# PennyMan_Ard_R3_Shield_v9_1.net
KiCad netlist of a schematic drawn in EAGLE
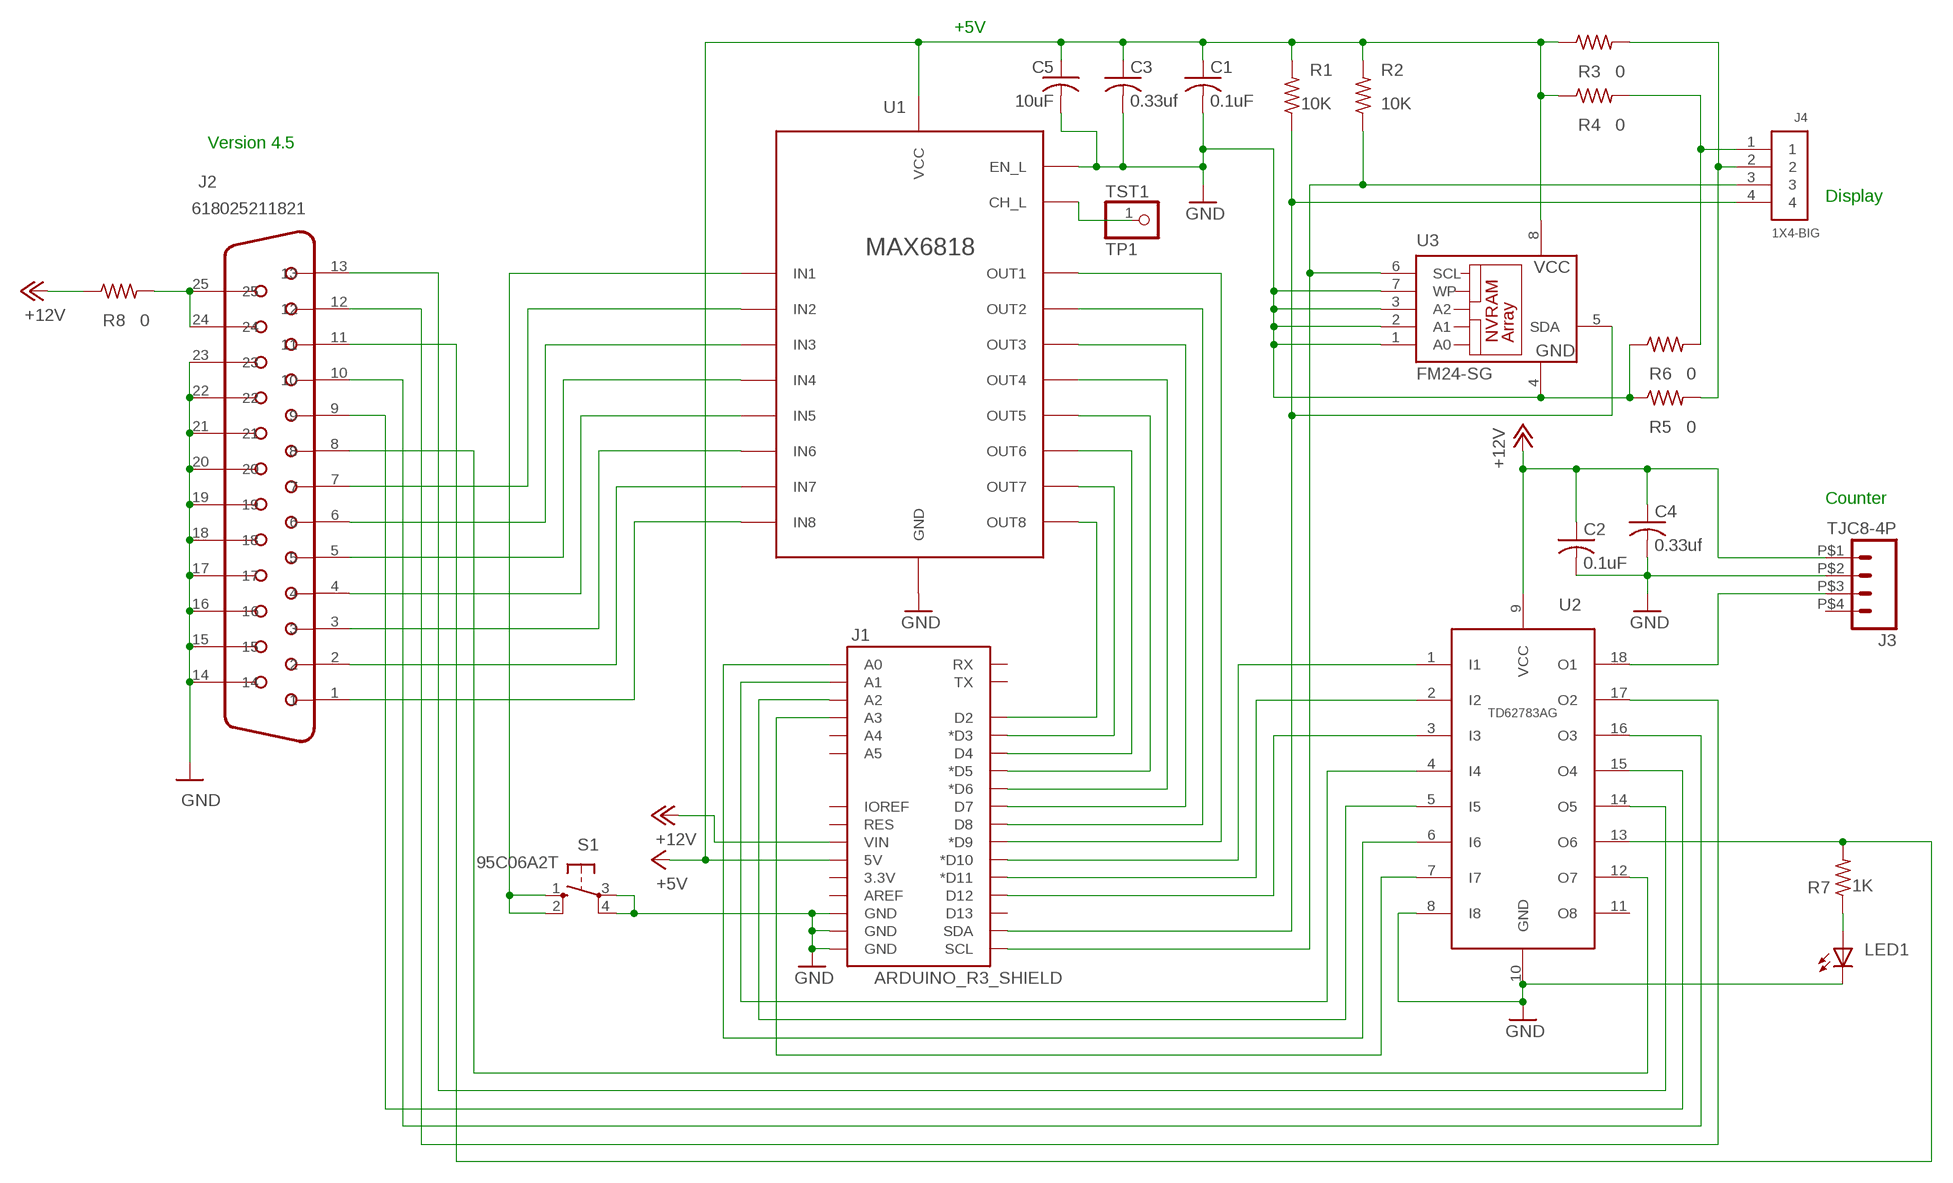
[diagram p0: schematic, sheet 1]

(export (version "E")
  (design (tool "Eeschema 10.0.6"))
  (components
    (comp (ref "C1")
      (value "0.1uF")
      (footprint "eagle-import:C0805")
      (libsource (lib "eagle-import") (part "C-USC0805"))
    )
    (comp (ref "C2")
      (value "0.1uF")
      (footprint "eagle-import:C0805")
      (libsource (lib "eagle-import") (part "C-USC0805"))
    )
    (comp (ref "C3")
      (value "0.33uf")
      (footprint "eagle-import:C1206")
      (libsource (lib "eagle-import") (part "C-USC1206"))
    )
    (comp (ref "C4")
      (value "0.33uf")
      (footprint "eagle-import:C1206")
      (libsource (lib "eagle-import") (part "C-USC1206"))
    )
    (comp (ref "C5")
      (value "10uF")
      (footprint "eagle-import:C1812")
      (libsource (lib "eagle-import") (part "C-USC1812"))
    )
    (comp (ref "J1")
      (value "ARDUINO_R3_SHIELD")
      (footprint "eagle-import:UNO_R3_SHIELD")
      (libsource (lib "eagle-import") (part "ARDUINO_R3_SHIELD"))
    )
    (comp (ref "J2")
      (value "618025211821")
      (footprint "eagle-import:618025211821")
      (libsource (lib "eagle-import") (part "618025211821"))
    )
    (comp (ref "J3")
      (value "TJC8-4P")
      (footprint "eagle-import:TJC8-4P")
      (libsource (lib "eagle-import") (part "TJC8-4P"))
    )
    (comp (ref "J4")
      (value "1X4-BIG")
      (footprint "eagle-import:1X04-BIG")
      (libsource (lib "eagle-import") (part "1X4-BIG"))
    )
    (comp (ref "LED1")
      (value "LEDSML0805")
      (footprint "eagle-import:SML0805")
      (libsource (lib "eagle-import") (part "LEDSML0805"))
    )
    (comp (ref "R1")
      (value "10K")
      (footprint "eagle-import:R0805")
      (libsource (lib "eagle-import") (part "R-US_R0805"))
    )
    (comp (ref "R2")
      (value "10K")
      (footprint "eagle-import:R0805")
      (libsource (lib "eagle-import") (part "R-US_R0805"))
    )
    (comp (ref "R3")
      (value "0")
      (footprint "eagle-import:R0805")
      (libsource (lib "eagle-import") (part "R-US_R0805"))
    )
    (comp (ref "R4")
      (value "0")
      (footprint "eagle-import:R0805")
      (libsource (lib "eagle-import") (part "R-US_R0805"))
    )
    (comp (ref "R5")
      (value "0")
      (footprint "eagle-import:R0805")
      (libsource (lib "eagle-import") (part "R-US_R0805"))
    )
    (comp (ref "R6")
      (value "0")
      (footprint "eagle-import:R0805")
      (libsource (lib "eagle-import") (part "R-US_R0805"))
    )
    (comp (ref "R7")
      (value "1K")
      (footprint "eagle-import:R0805")
      (libsource (lib "eagle-import") (part "R-US_R0805"))
    )
    (comp (ref "R8")
      (value "0")
      (footprint "eagle-import:R0805")
      (libsource (lib "eagle-import") (part "R-US_R0805"))
    )
    (comp (ref "S1")
      (value "95C06A2T")
      (footprint "eagle-import:B3F-10XX")
      (libsource (lib "eagle-import") (part "10-XX"))
    )
    (comp (ref "TST1")
      (value "TP1")
      (footprint "eagle-import:1X01")
      (libsource (lib "eagle-import") (part "PINHD-1X1"))
    )
    (comp (ref "U1")
      (value "MAX6818")
      (footprint "eagle-import:SSOP20")
      (libsource (lib "eagle-import") (part "MAX6818"))
    )
    (comp (ref "U2")
      (value "TD62783AG")
      (footprint "eagle-import:SOP18")
      (libsource (lib "eagle-import") (part "TD62783AG"))
    )
    (comp (ref "U3")
      (value "FM24-SG")
      (footprint "eagle-import:SO8")
      (libsource (lib "eagle-import") (part "FM24-SG"))
    )
  )
  (nets
    (net (code "1") (name "+5V") (class "Default")
      (node (ref "C1") (pin "1") (pinfunction "1_1") (pintype "passive"))
      (node (ref "C3") (pin "1") (pinfunction "1_1") (pintype "passive"))
      (node (ref "C5") (pin "1") (pinfunction "1_1") (pintype "passive"))
      (node (ref "J1") (pin "5V") (pinfunction "5V_5V") (pintype "bidirectional"))
      (node (ref "R1") (pin "2") (pinfunction "2_2") (pintype "passive"))
      (node (ref "R2") (pin "2") (pinfunction "2_2") (pintype "passive"))
      (node (ref "R3") (pin "1") (pinfunction "1_1") (pintype "passive"))
      (node (ref "R4") (pin "1") (pinfunction "1_1") (pintype "passive"))
      (node (ref "U1") (pin "VCC") (pinfunction "VCC_VCC") (pintype "bidirectional"))
      (node (ref "U3") (pin "8") (pinfunction "VCC_8") (pintype "power_in"))
    )
    (net (code "2") (name "+12V") (class "Default")
      (node (ref "C2") (pin "1") (pinfunction "1_1") (pintype "passive"))
      (node (ref "C4") (pin "1") (pinfunction "1_1") (pintype "passive"))
      (node (ref "J1") (pin "VIN") (pinfunction "VIN_VIN") (pintype "bidirectional"))
      (node (ref "J3") (pin "P$1") (pinfunction "1_P$1") (pintype "passive"))
      (node (ref "R8") (pin "1") (pinfunction "1_1") (pintype "passive"))
      (node (ref "U2") (pin "9") (pinfunction "VCC_9") (pintype "bidirectional"))
    )
    (net (code "3") (name "GND") (class "Default")
      (node (ref "C1") (pin "2") (pinfunction "2_2") (pintype "passive"))
      (node (ref "C2") (pin "2") (pinfunction "2_2") (pintype "passive"))
      (node (ref "C3") (pin "2") (pinfunction "2_2") (pintype "passive"))
      (node (ref "C4") (pin "2") (pinfunction "2_2") (pintype "passive"))
      (node (ref "C5") (pin "2") (pinfunction "2_2") (pintype "passive"))
      (node (ref "J1") (pin "GND@0") (pinfunction "GND_GND@0") (pintype "bidirectional"))
      (node (ref "J1") (pin "GND@1") (pinfunction "GND_GND@1") (pintype "bidirectional"))
      (node (ref "J1") (pin "GND@2") (pinfunction "GND_GND@2") (pintype "bidirectional"))
      (node (ref "J2") (pin "14") (pinfunction "14_14") (pintype "bidirectional"))
      (node (ref "J2") (pin "15") (pinfunction "15_15") (pintype "bidirectional"))
      (node (ref "J2") (pin "16") (pinfunction "16_16") (pintype "bidirectional"))
      (node (ref "J2") (pin "17") (pinfunction "17_17") (pintype "bidirectional"))
      (node (ref "J2") (pin "18") (pinfunction "18_18") (pintype "bidirectional"))
      (node (ref "J2") (pin "19") (pinfunction "19_19") (pintype "bidirectional"))
      (node (ref "J2") (pin "20") (pinfunction "20_20") (pintype "bidirectional"))
      (node (ref "J2") (pin "21") (pinfunction "21_21") (pintype "bidirectional"))
      (node (ref "J2") (pin "22") (pinfunction "22_22") (pintype "bidirectional"))
      (node (ref "J2") (pin "23") (pinfunction "23_23") (pintype "bidirectional"))
      (node (ref "J3") (pin "P$2") (pinfunction "2_P$2") (pintype "passive"))
      (node (ref "LED1") (pin "C") (pinfunction "C_C") (pintype "passive"))
      (node (ref "R5") (pin "1") (pinfunction "1_1") (pintype "passive"))
      (node (ref "R6") (pin "1") (pinfunction "1_1") (pintype "passive"))
      (node (ref "S1") (pin "3") (pinfunction "P_3") (pintype "passive"))
      (node (ref "S1") (pin "4") (pinfunction "P1_4") (pintype "passive"))
      (node (ref "U1") (pin "EN_L") (pinfunction "EN_L_EN_L") (pintype "bidirectional"))
      (node (ref "U1") (pin "GND") (pinfunction "GND_GND") (pintype "bidirectional"))
      (node (ref "U2") (pin "10") (pinfunction "GND_10") (pintype "bidirectional"))
      (node (ref "U2") (pin "8") (pinfunction "I8_8") (pintype "bidirectional"))
      (node (ref "U3") (pin "1") (pinfunction "A0_1") (pintype "passive"))
      (node (ref "U3") (pin "2") (pinfunction "A1_2") (pintype "passive"))
      (node (ref "U3") (pin "3") (pinfunction "A2_3") (pintype "passive"))
      (node (ref "U3") (pin "4") (pinfunction "GND_4") (pintype "power_in"))
      (node (ref "U3") (pin "7") (pinfunction "WP_7") (pintype "input"))
    )
    (net (code "4") (name "Net-(J1-*D3)") (class "Default")
      (node (ref "J1") (pin "D3") (pinfunction "*D3_D3") (pintype "bidirectional"))
      (node (ref "U1") (pin "OUT7") (pinfunction "OUT7_OUT7") (pintype "bidirectional"))
    )
    (net (code "5") (name "Net-(J1-*D5)") (class "Default")
      (node (ref "J1") (pin "D5") (pinfunction "*D5_D5") (pintype "bidirectional"))
      (node (ref "U1") (pin "OUT5") (pinfunction "OUT5_OUT5") (pintype "bidirectional"))
    )
    (net (code "6") (name "Net-(J1-*D6)") (class "Default")
      (node (ref "J1") (pin "D6") (pinfunction "*D6_D6") (pintype "bidirectional"))
      (node (ref "U1") (pin "OUT4") (pinfunction "OUT4_OUT4") (pintype "bidirectional"))
    )
    (net (code "7") (name "Net-(J1-*D9)") (class "Default")
      (node (ref "J1") (pin "D9") (pinfunction "*D9_D9") (pintype "bidirectional"))
      (node (ref "U1") (pin "OUT1") (pinfunction "OUT1_OUT1") (pintype "bidirectional"))
    )
    (net (code "8") (name "Net-(J1-*D10)") (class "Default")
      (node (ref "J1") (pin "D10") (pinfunction "*D10_D10") (pintype "bidirectional"))
      (node (ref "U2") (pin "1") (pinfunction "I1_1") (pintype "bidirectional"))
    )
    (net (code "9") (name "Net-(J1-*D11)") (class "Default")
      (node (ref "J1") (pin "D11") (pinfunction "*D11_D11") (pintype "bidirectional"))
      (node (ref "U2") (pin "2") (pinfunction "I2_2") (pintype "bidirectional"))
    )
    (net (code "10") (name "Net-(J1-PadD2)") (class "Default")
      (node (ref "J1") (pin "D2") (pinfunction "D2_D2") (pintype "bidirectional"))
      (node (ref "U1") (pin "OUT8") (pinfunction "OUT8_OUT8") (pintype "bidirectional"))
    )
    (net (code "11") (name "Net-(J1-PadD4)") (class "Default")
      (node (ref "J1") (pin "D4") (pinfunction "D4_D4") (pintype "bidirectional"))
      (node (ref "U1") (pin "OUT6") (pinfunction "OUT6_OUT6") (pintype "bidirectional"))
    )
    (net (code "12") (name "Net-(J1-PadD7)") (class "Default")
      (node (ref "J1") (pin "D7") (pinfunction "D7_D7") (pintype "bidirectional"))
      (node (ref "U1") (pin "OUT3") (pinfunction "OUT3_OUT3") (pintype "bidirectional"))
    )
    (net (code "13") (name "Net-(J1-PadD8)") (class "Default")
      (node (ref "J1") (pin "D8") (pinfunction "D8_D8") (pintype "bidirectional"))
      (node (ref "U1") (pin "OUT2") (pinfunction "OUT2_OUT2") (pintype "bidirectional"))
    )
    (net (code "14") (name "Net-(J2-Pad1)") (class "Default")
      (node (ref "J2") (pin "1") (pinfunction "1_1") (pintype "bidirectional"))
      (node (ref "U1") (pin "IN8") (pinfunction "IN8_IN8") (pintype "bidirectional"))
    )
    (net (code "15") (name "Net-(J2-Pad2)") (class "Default")
      (node (ref "J2") (pin "2") (pinfunction "2_2") (pintype "bidirectional"))
      (node (ref "U1") (pin "IN7") (pinfunction "IN7_IN7") (pintype "bidirectional"))
    )
    (net (code "16") (name "Net-(J2-Pad3)") (class "Default")
      (node (ref "J2") (pin "3") (pinfunction "3_3") (pintype "bidirectional"))
      (node (ref "U1") (pin "IN6") (pinfunction "IN6_IN6") (pintype "bidirectional"))
    )
    (net (code "17") (name "Net-(J2-Pad4)") (class "Default")
      (node (ref "J2") (pin "4") (pinfunction "4_4") (pintype "bidirectional"))
      (node (ref "U1") (pin "IN5") (pinfunction "IN5_IN5") (pintype "bidirectional"))
    )
    (net (code "18") (name "Net-(J2-Pad5)") (class "Default")
      (node (ref "J2") (pin "5") (pinfunction "5_5") (pintype "bidirectional"))
      (node (ref "U1") (pin "IN4") (pinfunction "IN4_IN4") (pintype "bidirectional"))
    )
    (net (code "19") (name "Net-(J2-Pad6)") (class "Default")
      (node (ref "J2") (pin "6") (pinfunction "6_6") (pintype "bidirectional"))
      (node (ref "U1") (pin "IN3") (pinfunction "IN3_IN3") (pintype "bidirectional"))
    )
    (net (code "20") (name "Net-(J2-Pad7)") (class "Default")
      (node (ref "J2") (pin "7") (pinfunction "7_7") (pintype "bidirectional"))
      (node (ref "U1") (pin "IN2") (pinfunction "IN2_IN2") (pintype "bidirectional"))
    )
    (net (code "21") (name "Net-(J2-Pad24)") (class "Default")
      (node (ref "J2") (pin "24") (pinfunction "24_24") (pintype "bidirectional"))
      (node (ref "J2") (pin "25") (pinfunction "25_25") (pintype "bidirectional"))
      (node (ref "R8") (pin "2") (pinfunction "2_2") (pintype "passive"))
    )
    (net (code "22") (name "Net-(J3-3)") (class "Default")
      (node (ref "J3") (pin "P$3") (pinfunction "3_P$3") (pintype "passive"))
      (node (ref "U2") (pin "18") (pinfunction "O1_18") (pintype "bidirectional"))
    )
    (net (code "23") (name "Net-(J4-Pad1)") (class "Default")
      (node (ref "J4") (pin "1") (pinfunction "1_1") (pintype "bidirectional"))
      (node (ref "R4") (pin "2") (pinfunction "2_2") (pintype "passive"))
      (node (ref "R6") (pin "2") (pinfunction "2_2") (pintype "passive"))
    )
    (net (code "24") (name "Net-(J4-Pad2)") (class "Default")
      (node (ref "J4") (pin "2") (pinfunction "2_2") (pintype "bidirectional"))
      (node (ref "R3") (pin "2") (pinfunction "2_2") (pintype "passive"))
      (node (ref "R5") (pin "2") (pinfunction "2_2") (pintype "passive"))
    )
    (net (code "25") (name "Net-(LED1-PadA)") (class "Default")
      (node (ref "LED1") (pin "A") (pinfunction "A_A") (pintype "passive"))
      (node (ref "R7") (pin "1") (pinfunction "1_1") (pintype "passive"))
    )
    (net (code "26") (name "Net-(S1-S)") (class "Default")
      (node (ref "S1") (pin "1") (pinfunction "S_1") (pintype "passive"))
      (node (ref "S1") (pin "2") (pinfunction "S1_2") (pintype "passive"))
      (node (ref "U1") (pin "IN1") (pinfunction "IN1_IN1") (pintype "bidirectional"))
    )
    (net (code "27") (name "Net-(TST1-Pad1)") (class "Default")
      (node (ref "TST1") (pin "1") (pinfunction "1_1") (pintype "passive"))
      (node (ref "U1") (pin "CH_L") (pinfunction "CH_L_CH_L") (pintype "bidirectional"))
    )
    (net (code "28") (name "Net-(U2-I3)") (class "Default")
      (node (ref "J1") (pin "D12") (pinfunction "D12_D12") (pintype "bidirectional"))
      (node (ref "U2") (pin "3") (pinfunction "I3_3") (pintype "bidirectional"))
    )
    (net (code "29") (name "Net-(U2-I4)") (class "Default")
      (node (ref "J1") (pin "A1") (pinfunction "A1_A1") (pintype "bidirectional"))
      (node (ref "U2") (pin "4") (pinfunction "I4_4") (pintype "bidirectional"))
    )
    (net (code "30") (name "Net-(U2-I5)") (class "Default")
      (node (ref "J1") (pin "A2") (pinfunction "A2_A2") (pintype "bidirectional"))
      (node (ref "U2") (pin "5") (pinfunction "I5_5") (pintype "bidirectional"))
    )
    (net (code "31") (name "Net-(U2-I6)") (class "Default")
      (node (ref "J1") (pin "A0") (pinfunction "A0_A0") (pintype "bidirectional"))
      (node (ref "U2") (pin "6") (pinfunction "I6_6") (pintype "bidirectional"))
    )
    (net (code "32") (name "Net-(U2-I7)") (class "Default")
      (node (ref "J1") (pin "A3") (pinfunction "A3_A3") (pintype "bidirectional"))
      (node (ref "U2") (pin "7") (pinfunction "I7_7") (pintype "bidirectional"))
    )
    (net (code "33") (name "Net-(U2-O2)") (class "Default")
      (node (ref "J2") (pin "12") (pinfunction "12_12") (pintype "bidirectional"))
      (node (ref "U2") (pin "17") (pinfunction "O2_17") (pintype "bidirectional"))
    )
    (net (code "34") (name "Net-(U2-O3)") (class "Default")
      (node (ref "J2") (pin "10") (pinfunction "10_10") (pintype "bidirectional"))
      (node (ref "U2") (pin "16") (pinfunction "O3_16") (pintype "bidirectional"))
    )
    (net (code "35") (name "Net-(U2-O4)") (class "Default")
      (node (ref "J2") (pin "9") (pinfunction "9_9") (pintype "bidirectional"))
      (node (ref "U2") (pin "15") (pinfunction "O4_15") (pintype "bidirectional"))
    )
    (net (code "36") (name "Net-(U2-O5)") (class "Default")
      (node (ref "J2") (pin "13") (pinfunction "13_13") (pintype "bidirectional"))
      (node (ref "U2") (pin "14") (pinfunction "O5_14") (pintype "bidirectional"))
    )
    (net (code "37") (name "Net-(U2-O6)") (class "Default")
      (node (ref "J2") (pin "11") (pinfunction "11_11") (pintype "bidirectional"))
      (node (ref "R7") (pin "2") (pinfunction "2_2") (pintype "passive"))
      (node (ref "U2") (pin "13") (pinfunction "O6_13") (pintype "bidirectional"))
    )
    (net (code "38") (name "Net-(U2-O7)") (class "Default")
      (node (ref "J2") (pin "8") (pinfunction "8_8") (pintype "bidirectional"))
      (node (ref "U2") (pin "12") (pinfunction "O7_12") (pintype "bidirectional"))
    )
    (net (code "39") (name "Net-(U3-SCL)") (class "Default")
      (node (ref "J1") (pin "SCL") (pinfunction "SCL_SCL") (pintype "bidirectional"))
      (node (ref "J4") (pin "3") (pinfunction "3_3") (pintype "bidirectional"))
      (node (ref "R2") (pin "1") (pinfunction "1_1") (pintype "passive"))
      (node (ref "U3") (pin "6") (pinfunction "SCL_6") (pintype "input"))
    )
    (net (code "40") (name "Net-(U3-SDA)") (class "Default")
      (node (ref "J1") (pin "SDA") (pinfunction "SDA_SDA") (pintype "bidirectional"))
      (node (ref "J4") (pin "4") (pinfunction "4_4") (pintype "bidirectional"))
      (node (ref "R1") (pin "1") (pinfunction "1_1") (pintype "passive"))
      (node (ref "U3") (pin "5") (pinfunction "SDA_5") (pintype "bidirectional"))
    )
    (net (code "41") (name "unconnected-(J1-Pad3.3V)") (class "Default")
      (node (ref "J1") (pin "3.3V") (pinfunction "3.3V_3.3V") (pintype "bidirectional"))
    )
    (net (code "42") (name "unconnected-(J1-PadA4)") (class "Default")
      (node (ref "J1") (pin "A4") (pinfunction "A4_A4") (pintype "bidirectional"))
    )
    (net (code "43") (name "unconnected-(J1-PadA5)") (class "Default")
      (node (ref "J1") (pin "A5") (pinfunction "A5_A5") (pintype "bidirectional"))
    )
    (net (code "44") (name "unconnected-(J1-PadAREF)") (class "Default")
      (node (ref "J1") (pin "AREF") (pinfunction "AREF_AREF") (pintype "bidirectional"))
    )
    (net (code "45") (name "unconnected-(J1-PadD13)") (class "Default")
      (node (ref "J1") (pin "D13") (pinfunction "D13_D13") (pintype "bidirectional"))
    )
    (net (code "46") (name "unconnected-(J1-PadIOREF)") (class "Default")
      (node (ref "J1") (pin "IOREF") (pinfunction "IOREF_IOREF") (pintype "bidirectional"))
    )
    (net (code "47") (name "unconnected-(J1-PadRES)") (class "Default")
      (node (ref "J1") (pin "RES") (pinfunction "RES_RES") (pintype "bidirectional"))
    )
    (net (code "48") (name "unconnected-(J1-PadRX)") (class "Default")
      (node (ref "J1") (pin "RX") (pinfunction "RX_RX") (pintype "bidirectional"))
    )
    (net (code "49") (name "unconnected-(J1-PadTX)") (class "Default")
      (node (ref "J1") (pin "TX") (pinfunction "TX_TX") (pintype "bidirectional"))
    )
    (net (code "50") (name "unconnected-(J3-4-PadP$4)") (class "Default")
      (node (ref "J3") (pin "P$4") (pinfunction "4_P$4") (pintype "passive"))
    )
    (net (code "51") (name "unconnected-(U2-O8-Pad11)") (class "Default")
      (node (ref "U2") (pin "11") (pinfunction "O8_11") (pintype "bidirectional"))
    )
  )
)
